# eps_bt1.net
KiCad netlist of a schematic drawn in Altium Designer
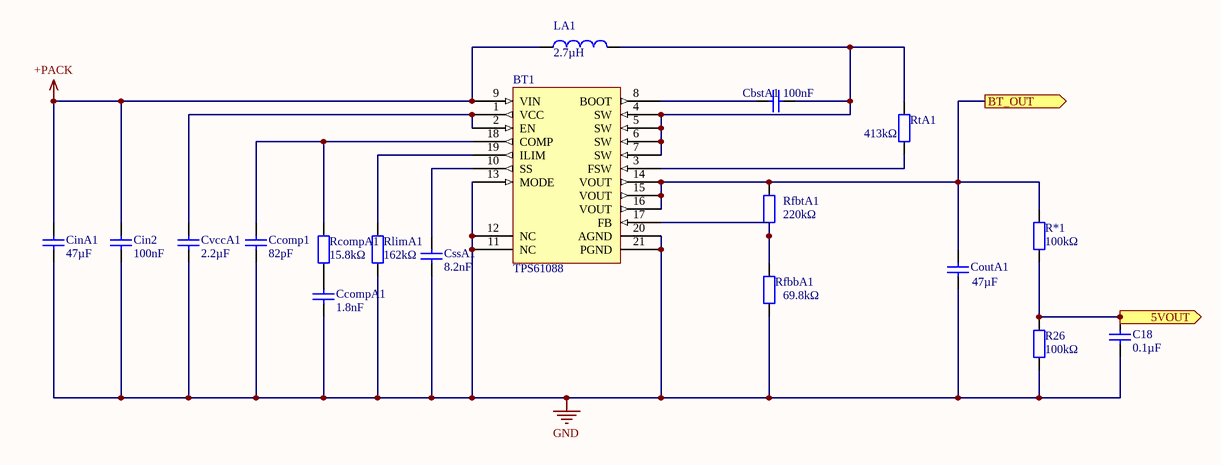
[diagram p0: eps_bt1.SchDoc]

(export (version "E")
  (design (tool "Eeschema 10.0.6"))
  (components
    (comp (ref "BT1")
      (value "TPS61088")
      (footprint "QFN50P450X350X100-21N")
      (description "Boost converter")
      (libsource (lib "heron-general") (part "TPS61088"))
    )
    (comp (ref "C18")
      (value "0.1µF")
      (footprint "1608[0603]")
      (description "Capacitor")
      (fields (field (name "PUBLISHER") "Altium Limited"))
      (libsource (lib "Miscellaneous Devices") (part "Cap"))
    )
    (comp (ref "CbstA1")
      (value "100nF")
      (footprint "1608[0603]")
      (description "Capacitor")
      (fields (field (name "PUBLISHER") "Altium Limited"))
      (libsource (lib "Miscellaneous Devices") (part "Cap"))
    )
    (comp (ref "Ccomp1")
      (value "82pF")
      (footprint "1608[0603]")
      (description "Capacitor")
      (fields (field (name "PUBLISHER") "Altium Limited"))
      (libsource (lib "Miscellaneous Devices") (part "Cap"))
    )
    (comp (ref "CcompA1")
      (value "1.8nF")
      (footprint "1608[0603]")
      (description "Capacitor")
      (fields (field (name "PUBLISHER") "Altium Limited"))
      (libsource (lib "Miscellaneous Devices") (part "Cap"))
    )
    (comp (ref "Cin2")
      (value "100nF")
      (footprint "1608[0603]")
      (description "Capacitor")
      (fields (field (name "PUBLISHER") "Altium Limited"))
      (libsource (lib "Miscellaneous Devices") (part "Cap"))
    )
    (comp (ref "CinA1")
      (value "47µF")
      (footprint "1608[0603]")
      (description "Capacitor")
      (fields (field (name "PUBLISHER") "Altium Limited"))
      (libsource (lib "Miscellaneous Devices") (part "Cap"))
    )
    (comp (ref "CoutA1")
      (value "47µF")
      (footprint "1608[0603]")
      (description "Capacitor")
      (fields (field (name "PUBLISHER") "Altium Limited"))
      (libsource (lib "Miscellaneous Devices") (part "Cap"))
    )
    (comp (ref "CssA1")
      (value "8.2nF")
      (footprint "1608[0603]")
      (description "Capacitor")
      (fields (field (name "PUBLISHER") "Altium Limited"))
      (libsource (lib "Miscellaneous Devices") (part "Cap"))
    )
    (comp (ref "CvccA1")
      (value "2.2µF")
      (footprint "1608[0603]")
      (description "Capacitor")
      (fields (field (name "PUBLISHER") "Altium Limited"))
      (libsource (lib "Miscellaneous Devices") (part "Cap"))
    )
    (comp (ref "LA1")
      (value "2.7µH")
      (footprint "1608[0603]")
      (description "Inductor")
      (fields (field (name "PUBLISHER") "Altium Limited"))
      (libsource (lib "Miscellaneous Devices") (part "Inductor"))
    )
    (comp (ref "R*1")
      (value "100kΩ")
      (footprint "1608[0603]")
      (description "Resistor")
      (fields (field (name "PUBLISHER") "Altium Limited"))
      (libsource (lib "") (part "Res2_1"))
    )
    (comp (ref "R26")
      (value "100kΩ")
      (footprint "1608[0603]")
      (description "Resistor")
      (fields (field (name "PUBLISHER") "Altium Limited"))
      (libsource (lib "") (part "Res2_1"))
    )
    (comp (ref "RcompA1")
      (value "15.8kΩ")
      (footprint "1608[0603]")
      (description "Resistor")
      (fields (field (name "PUBLISHER") "Altium Limited"))
      (libsource (lib "") (part "Res2_1"))
    )
    (comp (ref "RfbbA1")
      (value "69.8kΩ")
      (footprint "1608[0603]")
      (description "Resistor")
      (fields (field (name "PUBLISHER") "Altium Limited"))
      (libsource (lib "") (part "Res2_1"))
    )
    (comp (ref "RfbtA1")
      (value "220kΩ")
      (footprint "1608[0603]")
      (description "Resistor")
      (fields (field (name "PUBLISHER") "Altium Limited"))
      (libsource (lib "") (part "Res2_1"))
    )
    (comp (ref "RlimA1")
      (value "162kΩ")
      (footprint "1608[0603]")
      (description "Resistor")
      (fields (field (name "PUBLISHER") "Altium Limited"))
      (libsource (lib "") (part "Res2_1"))
    )
    (comp (ref "RtA1")
      (value "413kΩ")
      (footprint "1608[0603]")
      (description "Resistor")
      (fields (field (name "PUBLISHER") "Altium Limited"))
      (libsource (lib "Miscellaneous Devices") (part "Res2"))
    )
  )
  (nets
    (net (code "1") (name "+PACK") (class "Default")
      (node (ref "BT1") (pin "9") (pinfunction "VIN_9") (pintype "input"))
      (node (ref "Cin2") (pin "2") (pinfunction "2_2") (pintype "passive"))
      (node (ref "CinA1") (pin "2") (pinfunction "2_2") (pintype "passive"))
      (node (ref "LA1") (pin "1") (pinfunction "1_1") (pintype "passive"))
    )
    (net (code "2") (name "/5VOUT") (class "Default")
      (node (ref "C18") (pin "1") (pinfunction "1_1") (pintype "passive"))
      (node (ref "R*1") (pin "1") (pinfunction "1_1") (pintype "passive"))
      (node (ref "R26") (pin "2") (pinfunction "2_2") (pintype "passive"))
    )
    (net (code "3") (name "/BT_OUT") (class "Default")
      (node (ref "BT1") (pin "14") (pinfunction "VOUT_14") (pintype "output"))
      (node (ref "BT1") (pin "15") (pinfunction "VOUT_15") (pintype "output"))
      (node (ref "BT1") (pin "16") (pinfunction "VOUT_16") (pintype "output"))
      (node (ref "CoutA1") (pin "2") (pinfunction "2_2") (pintype "passive"))
      (node (ref "R*1") (pin "2") (pinfunction "2_2") (pintype "passive"))
      (node (ref "RfbtA1") (pin "2") (pinfunction "2_2") (pintype "passive"))
    )
    (net (code "4") (name "GND") (class "Default")
      (node (ref "BT1") (pin "11") (pinfunction "NC_11") (pintype "passive"))
      (node (ref "BT1") (pin "12") (pinfunction "NC_12") (pintype "passive"))
      (node (ref "BT1") (pin "13") (pinfunction "MODE_13") (pintype "input"))
      (node (ref "BT1") (pin "20") (pinfunction "AGND_20") (pintype "power_in"))
      (node (ref "BT1") (pin "21") (pinfunction "PGND_21") (pintype "power_in"))
      (node (ref "C18") (pin "2") (pinfunction "2_2") (pintype "passive"))
      (node (ref "Ccomp1") (pin "1") (pinfunction "1_1") (pintype "passive"))
      (node (ref "CcompA1") (pin "1") (pinfunction "1_1") (pintype "passive"))
      (node (ref "Cin2") (pin "1") (pinfunction "1_1") (pintype "passive"))
      (node (ref "CinA1") (pin "1") (pinfunction "1_1") (pintype "passive"))
      (node (ref "CoutA1") (pin "1") (pinfunction "1_1") (pintype "passive"))
      (node (ref "CssA1") (pin "1") (pinfunction "1_1") (pintype "passive"))
      (node (ref "CvccA1") (pin "1") (pinfunction "1_1") (pintype "passive"))
      (node (ref "R26") (pin "1") (pinfunction "1_1") (pintype "passive"))
      (node (ref "RfbbA1") (pin "1") (pinfunction "1_1") (pintype "passive"))
      (node (ref "RlimA1") (pin "1") (pinfunction "1_1") (pintype "passive"))
    )
    (net (code "5") (name "Net-(BT1-BOOT)") (class "Default")
      (node (ref "BT1") (pin "8") (pinfunction "BOOT_8") (pintype "output"))
      (node (ref "CbstA1") (pin "2") (pinfunction "2_2") (pintype "passive"))
    )
    (net (code "6") (name "Net-(BT1-COMP)") (class "Default")
      (node (ref "BT1") (pin "18") (pinfunction "COMP_18") (pintype "output"))
      (node (ref "Ccomp1") (pin "2") (pinfunction "2_2") (pintype "passive"))
      (node (ref "RcompA1") (pin "2") (pinfunction "2_2") (pintype "passive"))
    )
    (net (code "7") (name "Net-(BT1-EN)") (class "Default")
      (node (ref "BT1") (pin "1") (pinfunction "VCC_1") (pintype "output"))
      (node (ref "BT1") (pin "2") (pinfunction "EN_2") (pintype "input"))
      (node (ref "CvccA1") (pin "2") (pinfunction "2_2") (pintype "passive"))
    )
    (net (code "8") (name "Net-(BT1-FB)") (class "Default")
      (node (ref "BT1") (pin "17") (pinfunction "FB_17") (pintype "input"))
      (node (ref "RfbbA1") (pin "2") (pinfunction "2_2") (pintype "passive"))
      (node (ref "RfbtA1") (pin "1") (pinfunction "1_1") (pintype "passive"))
    )
    (net (code "9") (name "Net-(BT1-FSW)") (class "Default")
      (node (ref "BT1") (pin "3") (pinfunction "FSW_3") (pintype "input"))
      (node (ref "RtA1") (pin "2") (pinfunction "2_2") (pintype "passive"))
    )
    (net (code "10") (name "Net-(BT1-ILIM)") (class "Default")
      (node (ref "BT1") (pin "19") (pinfunction "ILIM_19") (pintype "output"))
      (node (ref "RlimA1") (pin "2") (pinfunction "2_2") (pintype "passive"))
    )
    (net (code "11") (name "Net-(BT1-SS)") (class "Default")
      (node (ref "BT1") (pin "10") (pinfunction "SS_10") (pintype "output"))
      (node (ref "CssA1") (pin "2") (pinfunction "2_2") (pintype "passive"))
    )
    (net (code "12") (name "Net-(BT1-SW-Pad4)") (class "Default")
      (node (ref "BT1") (pin "4") (pinfunction "SW_4") (pintype "input"))
      (node (ref "BT1") (pin "5") (pinfunction "SW_5") (pintype "input"))
      (node (ref "BT1") (pin "6") (pinfunction "SW_6") (pintype "input"))
      (node (ref "BT1") (pin "7") (pinfunction "SW_7") (pintype "input"))
      (node (ref "CbstA1") (pin "1") (pinfunction "1_1") (pintype "passive"))
      (node (ref "LA1") (pin "2") (pinfunction "2_2") (pintype "passive"))
      (node (ref "RtA1") (pin "1") (pinfunction "1_1") (pintype "passive"))
    )
    (net (code "13") (name "Net-(CcompA1-Pad2)") (class "Default")
      (node (ref "CcompA1") (pin "2") (pinfunction "2_2") (pintype "passive"))
      (node (ref "RcompA1") (pin "1") (pinfunction "1_1") (pintype "passive"))
    )
  )
)
